# saw-filter-adapter.net
KiCad netlist of a schematic drawn in EAGLE
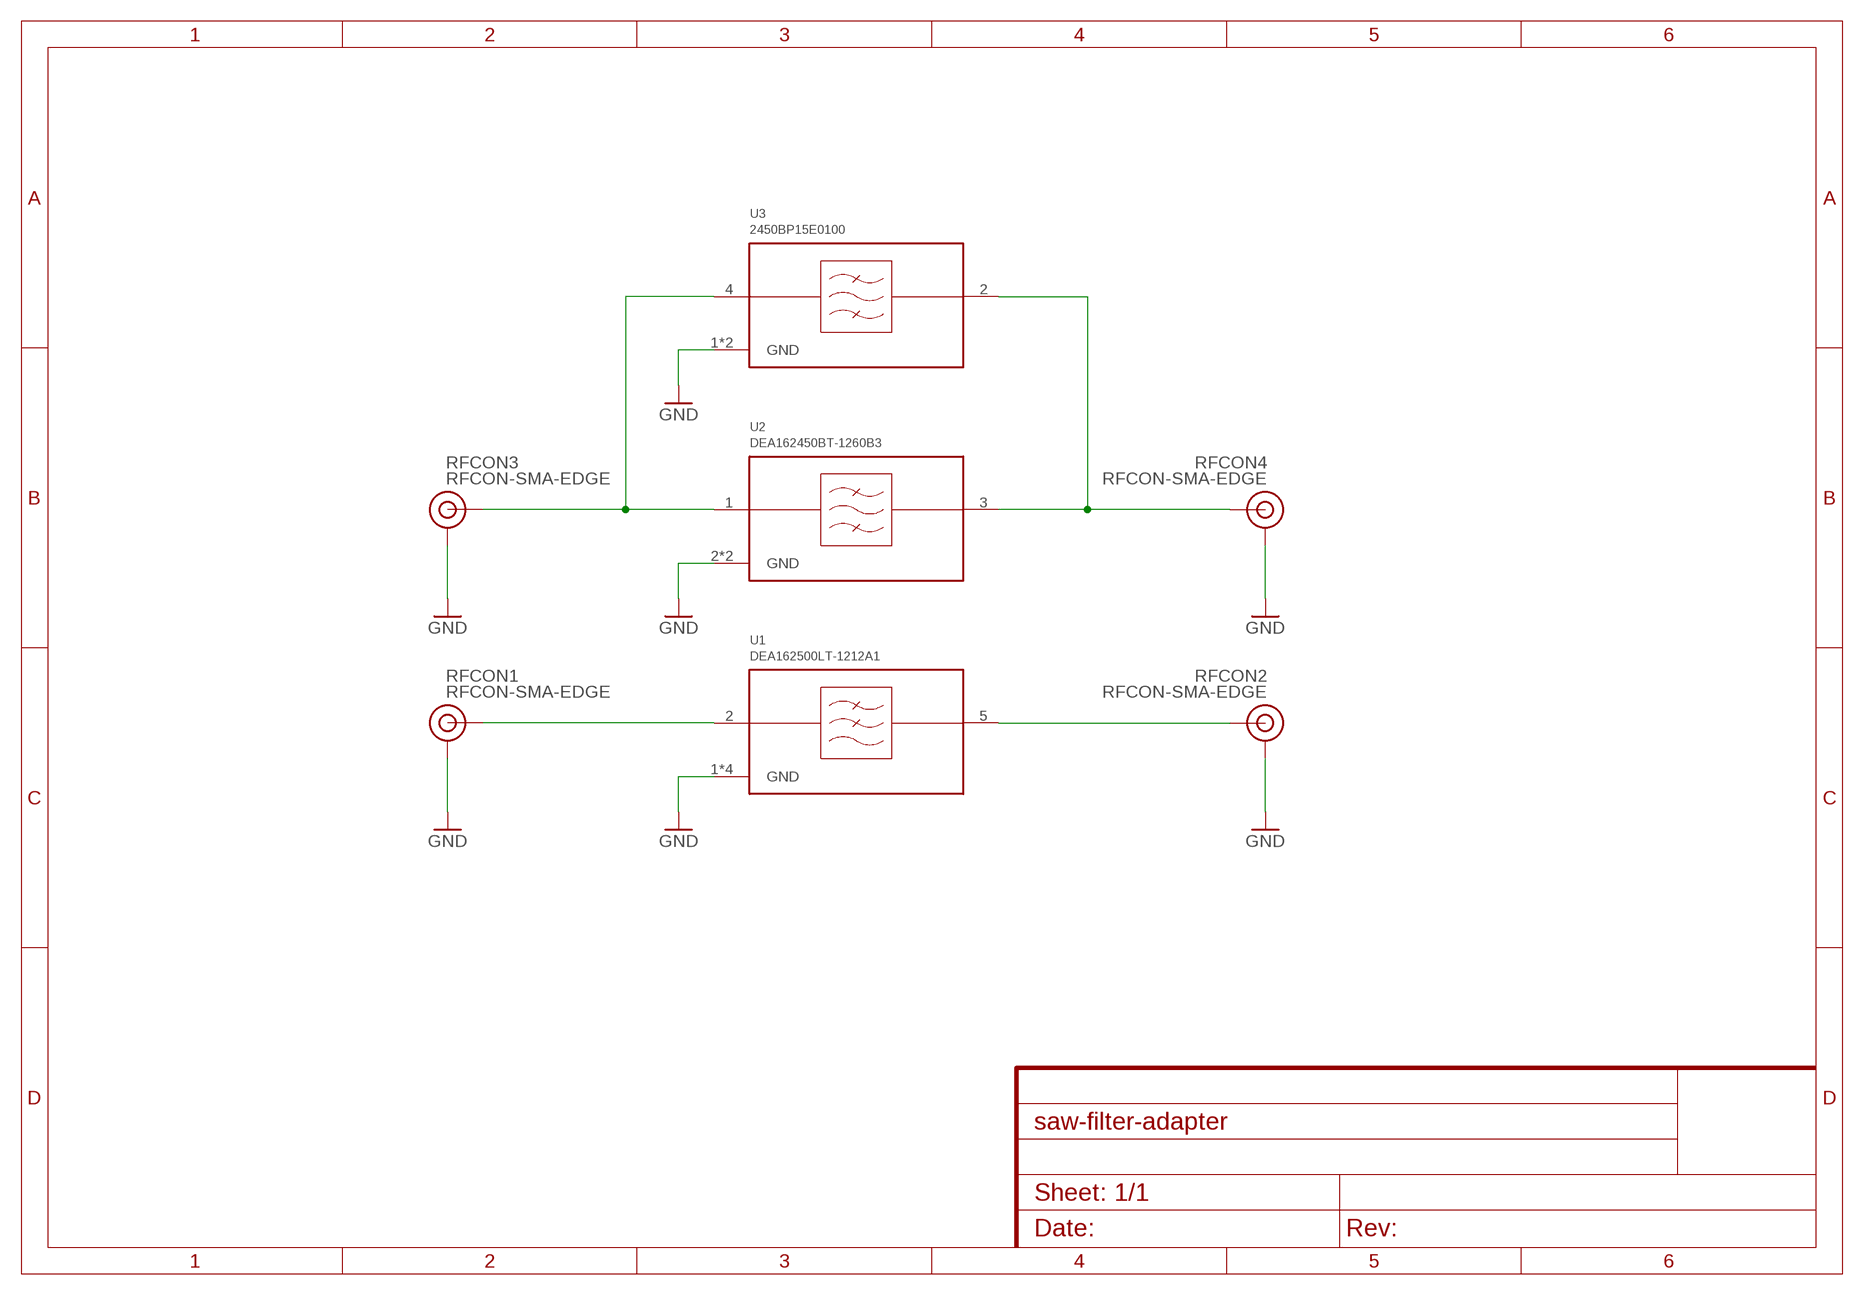
[diagram p0: schematic, sheet 1]

(export (version "E")
  (design (tool "Eeschema 10.0.6"))
  (components
    (comp (ref "RFCON1")
      (value "RFCON-SMA-EDGE")
      (footprint "eagle-import:SMA-EDGE")
      (libsource (lib "eagle-import") (part "RFCON-SMA-EDGE"))
    )
    (comp (ref "RFCON2")
      (value "RFCON-SMA-EDGE")
      (footprint "eagle-import:SMA-EDGE")
      (libsource (lib "eagle-import") (part "RFCON-SMA-EDGE"))
    )
    (comp (ref "RFCON3")
      (value "RFCON-SMA-EDGE")
      (footprint "eagle-import:SMA-EDGE")
      (libsource (lib "eagle-import") (part "RFCON-SMA-EDGE"))
    )
    (comp (ref "RFCON4")
      (value "RFCON-SMA-EDGE")
      (footprint "eagle-import:SMA-EDGE")
      (libsource (lib "eagle-import") (part "RFCON-SMA-EDGE"))
    )
    (comp (ref "U1")
      (value "DEA162500LT-1212A1")
      (footprint "eagle-import:DEA162500LT-1212A1")
      (libsource (lib "eagle-import") (part "DEA162500LT-1212A1"))
    )
    (comp (ref "U2")
      (value "DEA162450BT-1260B3")
      (footprint "eagle-import:DEA162450BT-1260B3")
      (libsource (lib "eagle-import") (part "DEA162450BT-1260B3"))
    )
    (comp (ref "U3")
      (value "2450BP15E0100")
      (footprint "eagle-import:2450BP15E0100")
      (libsource (lib "eagle-import") (part "2450BP15E0100"))
    )
  )
  (nets
    (net (code "1") (name "GND") (class "Default")
      (node (ref "RFCON1") (pin "GND@0") (pinfunction "GND_GND@0") (pintype "bidirectional"))
      (node (ref "RFCON1") (pin "GND@1") (pinfunction "GND_GND@1") (pintype "bidirectional"))
      (node (ref "RFCON1") (pin "GND@2") (pinfunction "GND_GND@2") (pintype "bidirectional"))
      (node (ref "RFCON1") (pin "GND@3") (pinfunction "GND_GND@3") (pintype "bidirectional"))
      (node (ref "RFCON2") (pin "GND@0") (pinfunction "GND_GND@0") (pintype "bidirectional"))
      (node (ref "RFCON2") (pin "GND@1") (pinfunction "GND_GND@1") (pintype "bidirectional"))
      (node (ref "RFCON2") (pin "GND@2") (pinfunction "GND_GND@2") (pintype "bidirectional"))
      (node (ref "RFCON2") (pin "GND@3") (pinfunction "GND_GND@3") (pintype "bidirectional"))
      (node (ref "RFCON3") (pin "GND@0") (pinfunction "GND_GND@0") (pintype "bidirectional"))
      (node (ref "RFCON3") (pin "GND@1") (pinfunction "GND_GND@1") (pintype "bidirectional"))
      (node (ref "RFCON3") (pin "GND@2") (pinfunction "GND_GND@2") (pintype "bidirectional"))
      (node (ref "RFCON3") (pin "GND@3") (pinfunction "GND_GND@3") (pintype "bidirectional"))
      (node (ref "RFCON4") (pin "GND@0") (pinfunction "GND_GND@0") (pintype "bidirectional"))
      (node (ref "RFCON4") (pin "GND@1") (pinfunction "GND_GND@1") (pintype "bidirectional"))
      (node (ref "RFCON4") (pin "GND@2") (pinfunction "GND_GND@2") (pintype "bidirectional"))
      (node (ref "RFCON4") (pin "GND@3") (pinfunction "GND_GND@3") (pintype "bidirectional"))
      (node (ref "U1") (pin "1") (pinfunction "GND_1") (pintype "bidirectional"))
      (node (ref "U1") (pin "3") (pinfunction "GND_3") (pintype "bidirectional"))
      (node (ref "U1") (pin "4") (pinfunction "GND_4") (pintype "bidirectional"))
      (node (ref "U1") (pin "6") (pinfunction "GND_6") (pintype "bidirectional"))
      (node (ref "U2") (pin "2") (pinfunction "GND_2") (pintype "bidirectional"))
      (node (ref "U2") (pin "4") (pinfunction "GND_4") (pintype "bidirectional"))
      (node (ref "U3") (pin "1") (pinfunction "GND_1") (pintype "bidirectional"))
      (node (ref "U3") (pin "3") (pinfunction "GND_3") (pintype "bidirectional"))
    )
    (net (code "2") (name "Net-(RFCON1-SIGNAL)") (class "Default")
      (node (ref "RFCON1") (pin "SIG") (pinfunction "SIGNAL_SIG") (pintype "bidirectional"))
      (node (ref "U1") (pin "2") (pinfunction "RFIN_2") (pintype "bidirectional"))
    )
    (net (code "3") (name "Net-(RFCON2-SIGNAL)") (class "Default")
      (node (ref "RFCON2") (pin "SIG") (pinfunction "SIGNAL_SIG") (pintype "bidirectional"))
      (node (ref "U1") (pin "5") (pinfunction "RFOUT_5") (pintype "bidirectional"))
    )
    (net (code "4") (name "Net-(RFCON3-SIGNAL)") (class "Default")
      (node (ref "RFCON3") (pin "SIG") (pinfunction "SIGNAL_SIG") (pintype "bidirectional"))
      (node (ref "U2") (pin "1") (pinfunction "RFIN_1") (pintype "bidirectional"))
      (node (ref "U3") (pin "4") (pinfunction "RFIN_4") (pintype "bidirectional"))
    )
    (net (code "5") (name "Net-(RFCON4-SIGNAL)") (class "Default")
      (node (ref "RFCON4") (pin "SIG") (pinfunction "SIGNAL_SIG") (pintype "bidirectional"))
      (node (ref "U2") (pin "3") (pinfunction "RFOUT_3") (pintype "bidirectional"))
      (node (ref "U3") (pin "2") (pinfunction "RFOUT_2") (pintype "bidirectional"))
    )
  )
)
